# DIO_1.net
KiCad netlist of a schematic drawn in Altium Designer
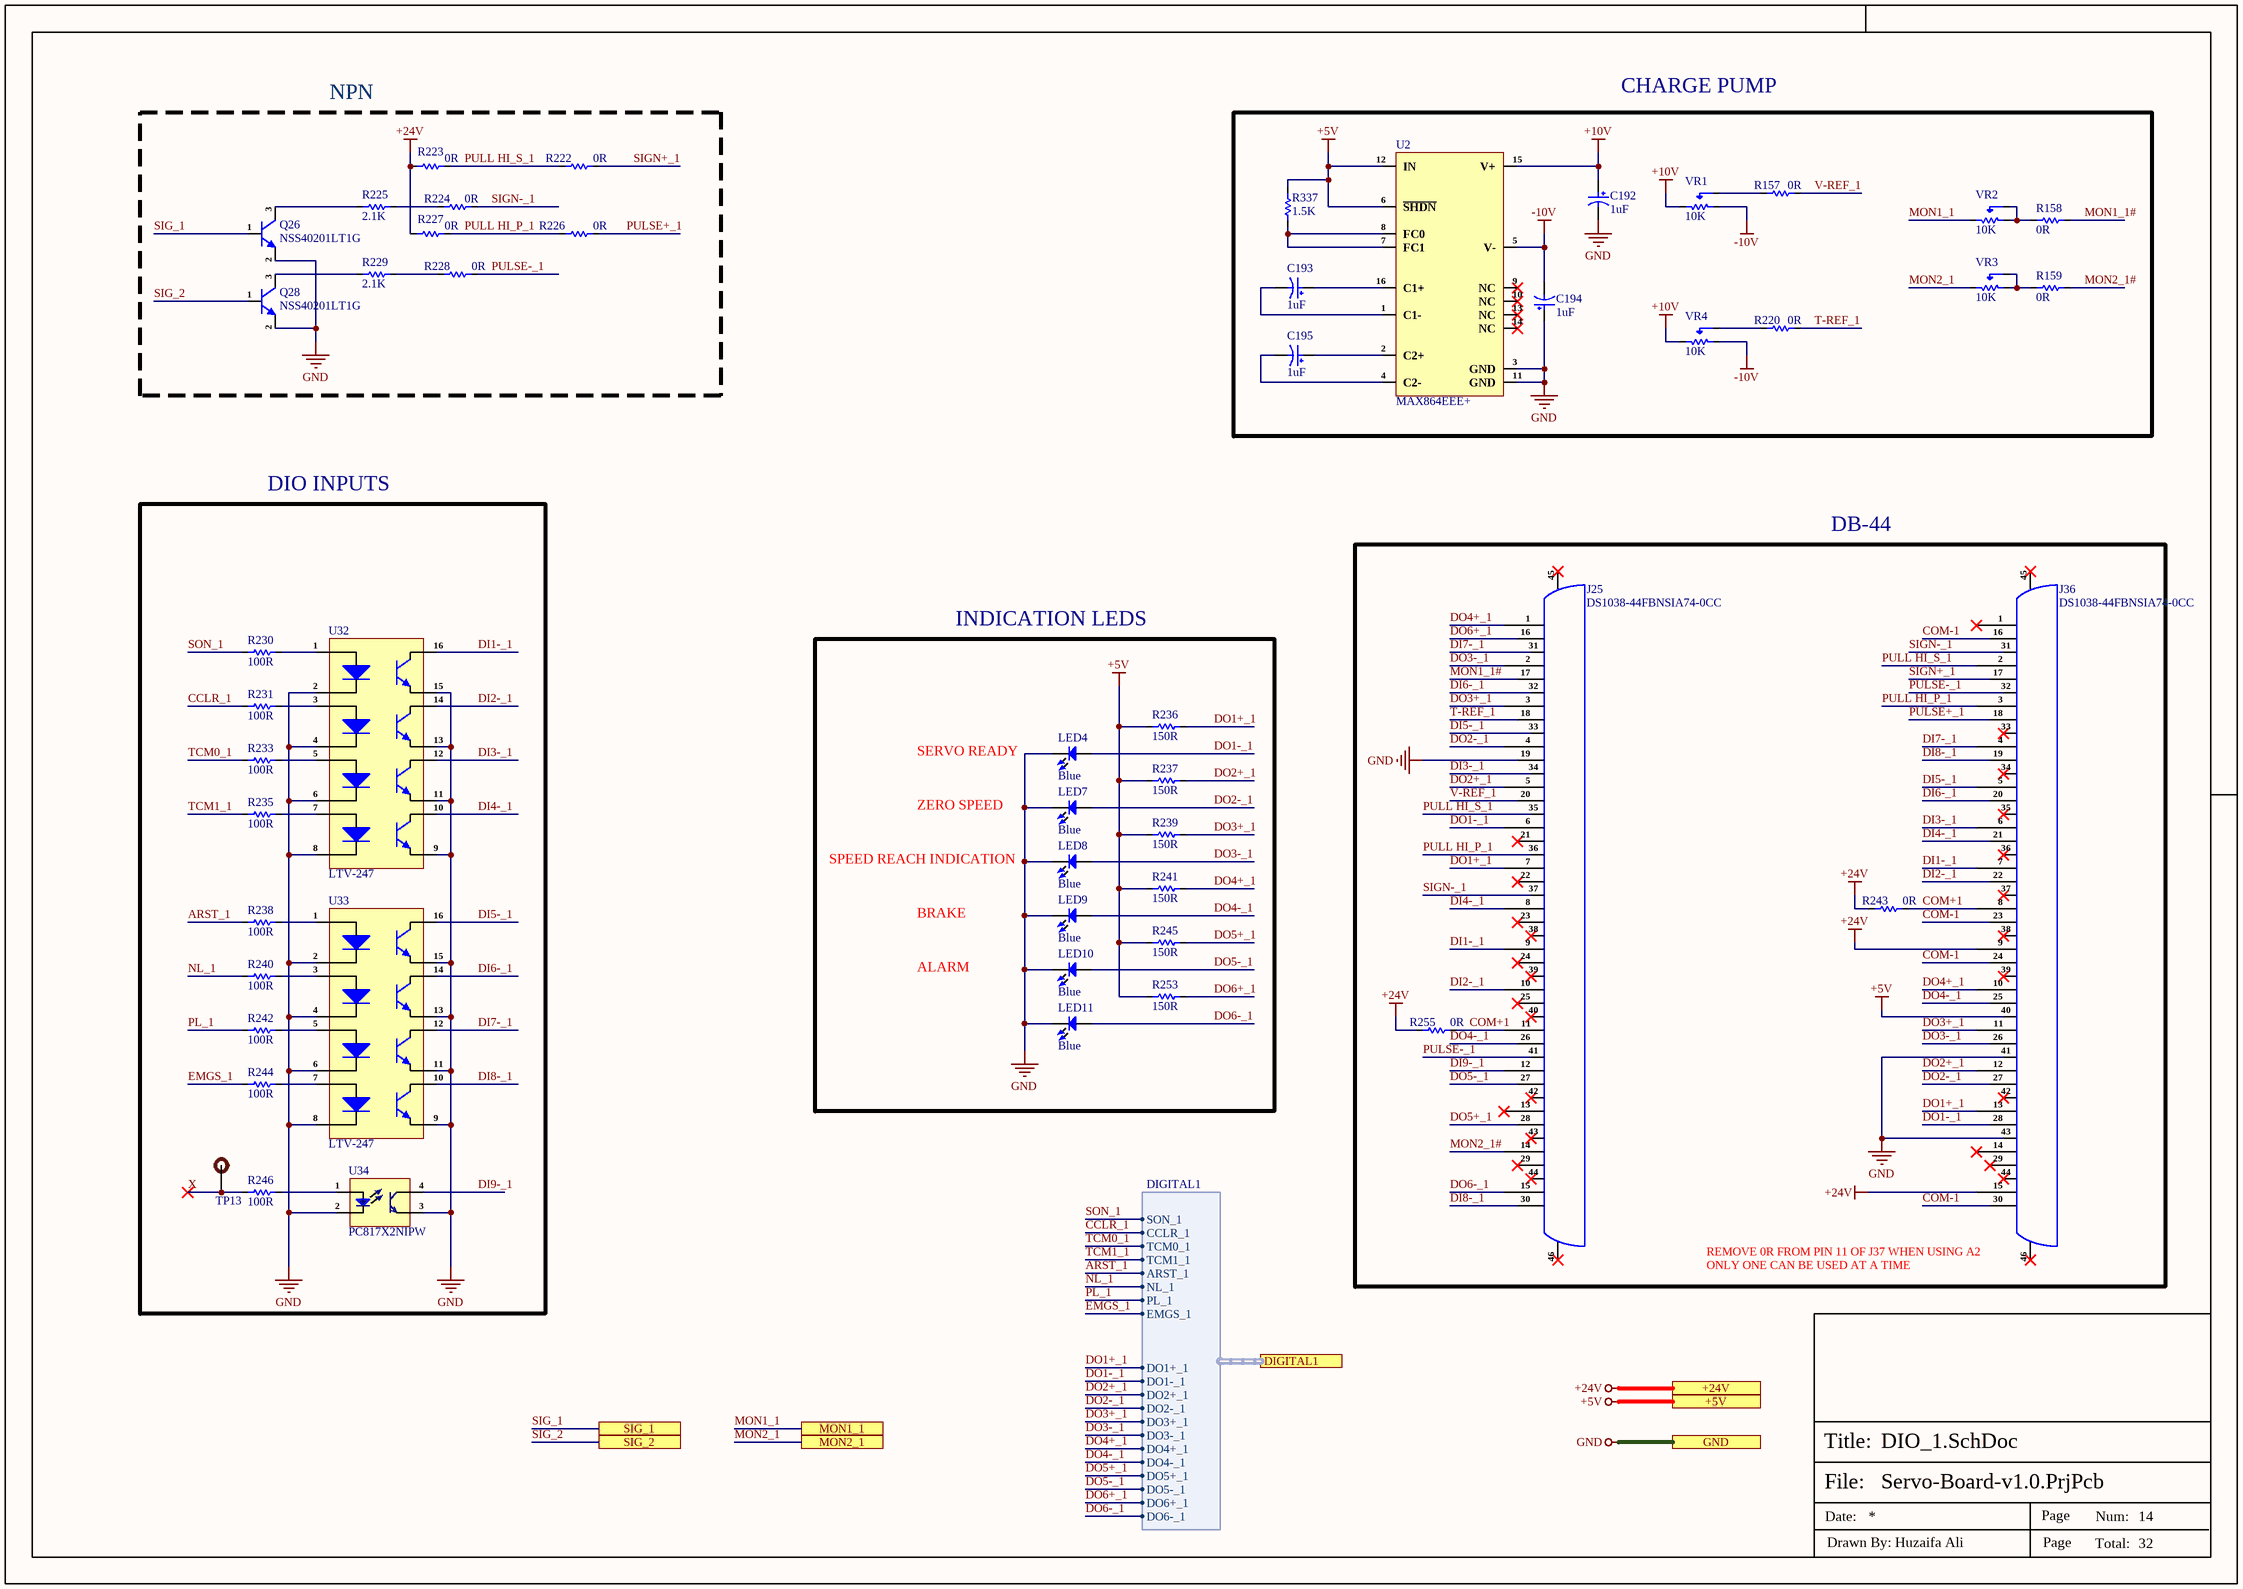
[diagram p0: DIO_1.SchDoc]

(export (version "E")
  (design (tool "Eeschema 10.0.6"))
  (components
    (comp (ref "C192")
      (value "1uF")
      (footprint "RVT1H1R0M0405")
      (description "1uF 50V 8mA@120Hz ±20% SMD,D4xL5.4mm Aluminum Electrolytic Capacitors - SMD ROHS")
      (fields (field (name "LCSC PART NUMBER") "C72491") (field (name "MANUFACTURER") "Roqang"))
      (libsource (lib "") (part "RVT1H1R0M0405_1"))
    )
    (comp (ref "C193")
      (value "1uF")
      (footprint "RVT1H1R0M0405")
      (description "1uF 50V 8mA@120Hz ±20% SMD,D4xL5.4mm Aluminum Electrolytic Capacitors - SMD ROHS")
      (fields (field (name "LCSC PART NUMBER") "C72491") (field (name "MANUFACTURER") "Roqang"))
      (libsource (lib "eSpark Libraries") (part "RVT1H1R0M0405"))
    )
    (comp (ref "C194")
      (value "1uF")
      (footprint "RVT1H1R0M0405")
      (description "1uF 50V 8mA@120Hz ±20% SMD,D4xL5.4mm Aluminum Electrolytic Capacitors - SMD ROHS")
      (fields (field (name "LCSC PART NUMBER") "C72491") (field (name "MANUFACTURER") "Roqang"))
      (libsource (lib "") (part "RVT1H1R0M0405_2"))
    )
    (comp (ref "C195")
      (value "1uF")
      (footprint "RVT1H1R0M0405")
      (description "1uF 50V 8mA@120Hz ±20% SMD,D4xL5.4mm Aluminum Electrolytic Capacitors - SMD ROHS")
      (fields (field (name "LCSC PART NUMBER") "C72491") (field (name "MANUFACTURER") "Roqang"))
      (libsource (lib "eSpark Libraries") (part "RVT1H1R0M0405"))
    )
    (comp (ref "J25")
      (value "DS1038-44FBNSIA74-0CC")
      (footprint "DS1038-44FBNSIA74-0CC")
      (description "44P Female D-Sub Right-Angle 3 1.5A -40℃~+105℃ Push-Pull D-Sub / VGA connector ROHS")
      (fields (field (name "MANUFACTURER") "CONNFLY Elec") (field (name "LCSC PART NUMBER") "C77844"))
      (libsource (lib "eSpark Libraries") (part "DS1038-44FBNSIA74-0CC"))
    )
    (comp (ref "J36")
      (value "DS1038-44FBNSIA74-0CC")
      (footprint "DS1038-44FBNSIA74-0CC")
      (description "44P Female D-Sub Right-Angle 3 1.5A -40℃~+105℃ Push-Pull D-Sub / VGA connector ROHS")
      (fields (field (name "MANUFACTURER") "CONNFLY Elec") (field (name "LCSC PART NUMBER") "C77844"))
      (libsource (lib "eSpark Libraries") (part "DS1038-44FBNSIA74-0CC"))
    )
    (comp (ref "LED4")
      (value "Blue")
      (footprint "LED-0603")
      (description "blue 0603 Light Emitting Diodes (LED) ROHS")
      (fields
        (field (name "MANUFACTURER") "Foshan NationStar Optoelectronics")
        (field (name "MANUFACTURER PART NUMBER") "NCD0603B3")
      )
      (libsource (lib "eSpark Libraries") (part "NCD0603B3"))
    )
    (comp (ref "LED7")
      (value "Blue")
      (footprint "LED-0603")
      (description "blue 0603 Light Emitting Diodes (LED) ROHS")
      (fields
        (field (name "MANUFACTURER") "Foshan NationStar Optoelectronics")
        (field (name "MANUFACTURER PART NUMBER") "NCD0603B3")
      )
      (libsource (lib "eSpark Libraries") (part "NCD0603B3"))
    )
    (comp (ref "LED8")
      (value "Blue")
      (footprint "LED-0603")
      (description "blue 0603 Light Emitting Diodes (LED) ROHS")
      (fields
        (field (name "MANUFACTURER") "Foshan NationStar Optoelectronics")
        (field (name "MANUFACTURER PART NUMBER") "NCD0603B3")
      )
      (libsource (lib "eSpark Libraries") (part "NCD0603B3"))
    )
    (comp (ref "LED9")
      (value "Blue")
      (footprint "LED-0603")
      (description "blue 0603 Light Emitting Diodes (LED) ROHS")
      (fields
        (field (name "MANUFACTURER") "Foshan NationStar Optoelectronics")
        (field (name "MANUFACTURER PART NUMBER") "NCD0603B3")
      )
      (libsource (lib "eSpark Libraries") (part "NCD0603B3"))
    )
    (comp (ref "LED10")
      (value "Blue")
      (footprint "LED-0603")
      (description "blue 0603 Light Emitting Diodes (LED) ROHS")
      (fields
        (field (name "MANUFACTURER") "Foshan NationStar Optoelectronics")
        (field (name "MANUFACTURER PART NUMBER") "NCD0603B3")
      )
      (libsource (lib "eSpark Libraries") (part "NCD0603B3"))
    )
    (comp (ref "LED11")
      (value "Blue")
      (footprint "LED-0603")
      (description "blue 0603 Light Emitting Diodes (LED) ROHS")
      (fields
        (field (name "MANUFACTURER") "Foshan NationStar Optoelectronics")
        (field (name "MANUFACTURER PART NUMBER") "NCD0603B3")
      )
      (libsource (lib "eSpark Libraries") (part "NCD0603B3"))
    )
    (comp (ref "Q26")
      (value "NSS40201LT1G")
      (footprint "SOT-23")
      (description "TRANS NPN 40V 2A SOT23-3")
      (fields (field (name "MANUFACTURER") "ON Semiconductor") (field (name "LCSC PART NUMBER") "C145175"))
      (libsource (lib "eSpark Libraries") (part "NSS40201LT1G"))
    )
    (comp (ref "Q28")
      (value "NSS40201LT1G")
      (footprint "SOT-23")
      (description "TRANS NPN 40V 2A SOT23-3")
      (fields (field (name "MANUFACTURER") "ON Semiconductor") (field (name "LCSC PART NUMBER") "C145175"))
      (libsource (lib "eSpark Libraries") (part "NSS40201LT1G"))
    )
    (comp (ref "R157")
      (value "0R")
      (footprint "Res-0402")
      (description "RES 0 OHM JUMPER 1/16W 0402")
      (fields
        (field (name "MANUFACTURER") "Yageo")
        (field (name "MANUFACTURER PART NUMBER") "RC0402FR-070RL")
      )
      (libsource (lib "eSpark Libraries") (part "RC0402FR-070RL"))
    )
    (comp (ref "R158")
      (value "0R")
      (footprint "Res-0402")
      (description "RES 0 OHM JUMPER 1/16W 0402")
      (fields
        (field (name "MANUFACTURER") "Yageo")
        (field (name "MANUFACTURER PART NUMBER") "RC0402FR-070RL")
      )
      (libsource (lib "eSpark Libraries") (part "RC0402FR-070RL"))
    )
    (comp (ref "R159")
      (value "0R")
      (footprint "Res-0402")
      (description "RES 0 OHM JUMPER 1/16W 0402")
      (fields
        (field (name "MANUFACTURER") "Yageo")
        (field (name "MANUFACTURER PART NUMBER") "RC0402FR-070RL")
      )
      (libsource (lib "eSpark Libraries") (part "RC0402FR-070RL"))
    )
    (comp (ref "R220")
      (value "0R")
      (footprint "Res-0402")
      (description "RES 0 OHM JUMPER 1/16W 0402")
      (fields
        (field (name "MANUFACTURER") "Yageo")
        (field (name "MANUFACTURER PART NUMBER") "RC0402FR-070RL")
      )
      (libsource (lib "eSpark Libraries") (part "RC0402FR-070RL"))
    )
    (comp (ref "R222")
      (value "0R")
      (footprint "Res-0603")
      (description "RES 0 OHM JUMPER 1/10W 0603")
      (fields
        (field (name "MANUFACTURER") "Yageo")
        (field (name "MANUFACTURER PART NUMBER") "RC0603JR-070RL")
      )
      (libsource (lib "eSpark Libraries") (part "RC0603JR-070RL"))
    )
    (comp (ref "R223")
      (value "0R")
      (footprint "Res-0603")
      (description "RES 0 OHM JUMPER 1/10W 0603")
      (fields
        (field (name "MANUFACTURER") "Yageo")
        (field (name "MANUFACTURER PART NUMBER") "RC0603JR-070RL")
      )
      (libsource (lib "eSpark Libraries") (part "RC0603JR-070RL"))
    )
    (comp (ref "R224")
      (value "0R")
      (footprint "Res-0603")
      (description "RES 0 OHM JUMPER 1/10W 0603")
      (fields
        (field (name "MANUFACTURER") "Yageo")
        (field (name "MANUFACTURER PART NUMBER") "RC0603JR-070RL")
      )
      (libsource (lib "eSpark Libraries") (part "RC0603JR-070RL"))
    )
    (comp (ref "R225")
      (value "2.1K")
      (footprint "Res-0603")
      (description "RES SMD 2.1K OHM 0.1% 1/10W 0603")
      (fields
        (field (name "MANUFACTURER") "Yageo")
        (field (name "MANUFACTURER PART NUMBER") "RT0603BRD072K1L")
      )
      (libsource (lib "eSpark Libraries") (part "RT0603BRD072K1L"))
    )
    (comp (ref "R226")
      (value "0R")
      (footprint "Res-0603")
      (description "RES 0 OHM JUMPER 1/10W 0603")
      (fields
        (field (name "MANUFACTURER") "Yageo")
        (field (name "MANUFACTURER PART NUMBER") "RC0603JR-070RL")
      )
      (libsource (lib "eSpark Libraries") (part "RC0603JR-070RL"))
    )
    (comp (ref "R227")
      (value "0R")
      (footprint "Res-0603")
      (description "RES 0 OHM JUMPER 1/10W 0603")
      (fields
        (field (name "MANUFACTURER") "Yageo")
        (field (name "MANUFACTURER PART NUMBER") "RC0603JR-070RL")
      )
      (libsource (lib "eSpark Libraries") (part "RC0603JR-070RL"))
    )
    (comp (ref "R228")
      (value "0R")
      (footprint "Res-0603")
      (description "RES 0 OHM JUMPER 1/10W 0603")
      (fields
        (field (name "MANUFACTURER") "Yageo")
        (field (name "MANUFACTURER PART NUMBER") "RC0603JR-070RL")
      )
      (libsource (lib "eSpark Libraries") (part "RC0603JR-070RL"))
    )
    (comp (ref "R229")
      (value "2.1K")
      (footprint "Res-0603")
      (description "RES SMD 2.1K OHM 0.1% 1/10W 0603")
      (fields
        (field (name "MANUFACTURER") "Yageo")
        (field (name "MANUFACTURER PART NUMBER") "RT0603BRD072K1L")
      )
      (libsource (lib "eSpark Libraries") (part "RT0603BRD072K1L"))
    )
    (comp (ref "R230")
      (value "100R")
      (footprint "Res-0402")
      (description "RES 100 OHM 1% 1/16W 0402")
      (fields
        (field (name "MANUFACTURER") "Yageo")
        (field (name "MANUFACTURER PART NUMBER") "RC0402FR-07100RL")
      )
      (libsource (lib "eSpark Libraries") (part "RC0402FR-07100RL"))
    )
    (comp (ref "R231")
      (value "100R")
      (footprint "Res-0402")
      (description "RES 100 OHM 1% 1/16W 0402")
      (fields
        (field (name "MANUFACTURER") "Yageo")
        (field (name "MANUFACTURER PART NUMBER") "RC0402FR-07100RL")
      )
      (libsource (lib "eSpark Libraries") (part "RC0402FR-07100RL"))
    )
    (comp (ref "R233")
      (value "100R")
      (footprint "Res-0402")
      (description "RES 100 OHM 1% 1/16W 0402")
      (fields
        (field (name "MANUFACTURER") "Yageo")
        (field (name "MANUFACTURER PART NUMBER") "RC0402FR-07100RL")
      )
      (libsource (lib "eSpark Libraries") (part "RC0402FR-07100RL"))
    )
    (comp (ref "R235")
      (value "100R")
      (footprint "Res-0402")
      (description "RES 100 OHM 1% 1/16W 0402")
      (fields
        (field (name "MANUFACTURER") "Yageo")
        (field (name "MANUFACTURER PART NUMBER") "RC0402FR-07100RL")
      )
      (libsource (lib "eSpark Libraries") (part "RC0402FR-07100RL"))
    )
    (comp (ref "R236")
      (value "150R")
      (footprint "Res-0603")
      (description "RES 150 OHM 0.5% 1/10W 0603")
      (fields
        (field (name "MANUFACTURER") "Yageo")
        (field (name "MANUFACTURER PART NUMBER") "RC0603DR-07150RL")
      )
      (libsource (lib "eSpark Libraries") (part "RC0603DR-07150RL"))
    )
    (comp (ref "R237")
      (value "150R")
      (footprint "Res-0603")
      (description "RES 150 OHM 0.5% 1/10W 0603")
      (fields
        (field (name "MANUFACTURER") "Yageo")
        (field (name "MANUFACTURER PART NUMBER") "RC0603DR-07150RL")
      )
      (libsource (lib "eSpark Libraries") (part "RC0603DR-07150RL"))
    )
    (comp (ref "R238")
      (value "100R")
      (footprint "Res-0402")
      (description "RES 100 OHM 1% 1/16W 0402")
      (fields
        (field (name "MANUFACTURER") "Yageo")
        (field (name "MANUFACTURER PART NUMBER") "RC0402FR-07100RL")
      )
      (libsource (lib "eSpark Libraries") (part "RC0402FR-07100RL"))
    )
    (comp (ref "R239")
      (value "150R")
      (footprint "Res-0603")
      (description "RES 150 OHM 0.5% 1/10W 0603")
      (fields
        (field (name "MANUFACTURER") "Yageo")
        (field (name "MANUFACTURER PART NUMBER") "RC0603DR-07150RL")
      )
      (libsource (lib "eSpark Libraries") (part "RC0603DR-07150RL"))
    )
    (comp (ref "R240")
      (value "100R")
      (footprint "Res-0402")
      (description "RES 100 OHM 1% 1/16W 0402")
      (fields
        (field (name "MANUFACTURER") "Yageo")
        (field (name "MANUFACTURER PART NUMBER") "RC0402FR-07100RL")
      )
      (libsource (lib "eSpark Libraries") (part "RC0402FR-07100RL"))
    )
    (comp (ref "R241")
      (value "150R")
      (footprint "Res-0603")
      (description "RES 150 OHM 0.5% 1/10W 0603")
      (fields
        (field (name "MANUFACTURER") "Yageo")
        (field (name "MANUFACTURER PART NUMBER") "RC0603DR-07150RL")
      )
      (libsource (lib "eSpark Libraries") (part "RC0603DR-07150RL"))
    )
    (comp (ref "R242")
      (value "100R")
      (footprint "Res-0402")
      (description "RES 100 OHM 1% 1/16W 0402")
      (fields
        (field (name "MANUFACTURER") "Yageo")
        (field (name "MANUFACTURER PART NUMBER") "RC0402FR-07100RL")
      )
      (libsource (lib "eSpark Libraries") (part "RC0402FR-07100RL"))
    )
    (comp (ref "R243")
      (value "0R")
      (footprint "Res-0402")
      (description "RES 0 OHM JUMPER 1/16W 0402")
      (fields
        (field (name "MANUFACTURER") "Yageo")
        (field (name "MANUFACTURER PART NUMBER") "RC0402FR-070RL")
      )
      (libsource (lib "eSpark Libraries") (part "RC0402FR-070RL"))
    )
    (comp (ref "R244")
      (value "100R")
      (footprint "Res-0402")
      (description "RES 100 OHM 1% 1/16W 0402")
      (fields
        (field (name "MANUFACTURER") "Yageo")
        (field (name "MANUFACTURER PART NUMBER") "RC0402FR-07100RL")
      )
      (libsource (lib "eSpark Libraries") (part "RC0402FR-07100RL"))
    )
    (comp (ref "R245")
      (value "150R")
      (footprint "Res-0603")
      (description "RES 150 OHM 0.5% 1/10W 0603")
      (fields
        (field (name "MANUFACTURER") "Yageo")
        (field (name "MANUFACTURER PART NUMBER") "RC0603DR-07150RL")
      )
      (libsource (lib "eSpark Libraries") (part "RC0603DR-07150RL"))
    )
    (comp (ref "R246")
      (value "100R")
      (footprint "Res-0402")
      (description "RES 100 OHM 1% 1/16W 0402")
      (fields
        (field (name "MANUFACTURER") "Yageo")
        (field (name "MANUFACTURER PART NUMBER") "RC0402FR-07100RL")
      )
      (libsource (lib "eSpark Libraries") (part "RC0402FR-07100RL"))
    )
    (comp (ref "R253")
      (value "150R")
      (footprint "Res-0603")
      (description "RES 150 OHM 0.5% 1/10W 0603")
      (fields
        (field (name "MANUFACTURER") "Yageo")
        (field (name "MANUFACTURER PART NUMBER") "RC0603DR-07150RL")
      )
      (libsource (lib "eSpark Libraries") (part "RC0603DR-07150RL"))
    )
    (comp (ref "R255")
      (value "0R")
      (footprint "Res-0603")
      (description "RES 0 OHM JUMPER 1/10W 0603")
      (fields
        (field (name "MANUFACTURER") "Yageo")
        (field (name "MANUFACTURER PART NUMBER") "RC0603JR-070RL")
      )
      (libsource (lib "eSpark Libraries") (part "RC0603JR-070RL"))
    )
    (comp (ref "R337")
      (value "1.5K")
      (footprint "Res-0402")
      (description "RES 1.5K OHM 1% 1/16W 0402")
      (fields
        (field (name "MANUFACTURER") "Yageo")
        (field (name "MANUFACTURER PART NUMBER") "RC0402FR-071K5L")
      )
      (libsource (lib "eSpark Libraries") (part "RC0402FR-071K5L"))
    )
    (comp (ref "TP13")
      (value "TEST POINT")
      (footprint "Test-point")
      (description "Test Point ON")
      (libsource (lib "eSpark Libraries") (part "TEST POINT"))
    )
    (comp (ref "U2")
      (value "MAX864EEE+")
      (footprint "16-QSOP")
      (description "IC REG CHARGE PUMP INV 16QSOP")
      (fields (field (name "MANUFACTURER") "Maxim"))
      (libsource (lib "eSpark Libraries") (part "MAX864EEE+"))
    )
    (comp (ref "U32")
      (value "LTV-247")
      (footprint "16-SO")
      (description "OPTOISO 3.75KV 4CH TRANS 16SO")
      (fields (field (name "MANUFACTURER") "Vishay Lite-On") (field (name "LCSC PART NUMBER") "C115451"))
      (libsource (lib "eSpark Libraries") (part "LTV-247"))
    )
    (comp (ref "U33")
      (value "LTV-247")
      (footprint "16-SO")
      (description "OPTOISO 3.75KV 4CH TRANS 16SO")
      (fields (field (name "MANUFACTURER") "Vishay Lite-On") (field (name "LCSC PART NUMBER") "C115451"))
      (libsource (lib "eSpark Libraries") (part "LTV-247"))
    )
    (comp (ref "U34")
      (value "PC817X2NIPW")
      (footprint "PC817X2NIPW")
      (description "Optoisolator Output Channel 4-SMD")
      (fields (field (name "MANUFACTURER") "Sharp") (field (name "LCSC PART NUMBER") "C2840443"))
      (libsource (lib "eSpark Libraries") (part "PC817X2NIPW"))
    )
    (comp (ref "VR1")
      (value "10K")
      (footprint "3362P-1-103")
      (description "TRIMMER 10K OHM 0.5W PC PIN TOP")
      (fields (field (name "LCSC PART NUMBER") "C118956") (field (name "MANUFACTURER") "Bourns"))
      (libsource (lib "eSpark Libraries") (part "3362P-1-103"))
    )
    (comp (ref "VR2")
      (value "10K")
      (footprint "3362P-1-103")
      (description "TRIMMER 10K OHM 0.5W PC PIN TOP")
      (fields (field (name "LCSC PART NUMBER") "C118956") (field (name "MANUFACTURER") "Bourns"))
      (libsource (lib "eSpark Libraries") (part "3362P-1-103"))
    )
    (comp (ref "VR3")
      (value "10K")
      (footprint "3362P-1-103")
      (description "TRIMMER 10K OHM 0.5W PC PIN TOP")
      (fields (field (name "LCSC PART NUMBER") "C118956") (field (name "MANUFACTURER") "Bourns"))
      (libsource (lib "eSpark Libraries") (part "3362P-1-103"))
    )
    (comp (ref "VR4")
      (value "10K")
      (footprint "3362P-1-103")
      (description "TRIMMER 10K OHM 0.5W PC PIN TOP")
      (fields (field (name "LCSC PART NUMBER") "C118956") (field (name "MANUFACTURER") "Bourns"))
      (libsource (lib "eSpark Libraries") (part "3362P-1-103"))
    )
  )
  (nets
    (net (code "2") (name "+5V") (class "Default")
      (node (ref "J36") (pin "40") (pinfunction "40_40") (pintype "passive"))
      (node (ref "R236") (pin "1") (pinfunction "1_1") (pintype "passive"))
      (node (ref "R237") (pin "1") (pinfunction "1_1") (pintype "passive"))
      (node (ref "R239") (pin "1") (pinfunction "1_1") (pintype "passive"))
      (node (ref "R241") (pin "1") (pinfunction "1_1") (pintype "passive"))
      (node (ref "R245") (pin "1") (pinfunction "1_1") (pintype "passive"))
      (node (ref "R253") (pin "1") (pinfunction "1_1") (pintype "passive"))
      (node (ref "R337") (pin "2") (pinfunction "2_2") (pintype "passive"))
      (node (ref "U2") (pin "12") (pinfunction "IN_12") (pintype "passive"))
      (node (ref "U2") (pin "6") (pinfunction "~{SHDN}_6") (pintype "passive"))
    )
    (net (code "3") (name "+10V") (class "Default")
      (node (ref "C192") (pin "1") (pintype "passive"))
      (node (ref "U2") (pin "15") (pinfunction "V+_15") (pintype "passive"))
      (node (ref "VR1") (pin "3") (pinfunction "CW_3") (pintype "passive"))
      (node (ref "VR4") (pin "3") (pinfunction "CW_3") (pintype "passive"))
    )
    (net (code "4") (name "+24V") (class "Default")
      (node (ref "J36") (pin "15") (pinfunction "15_15") (pintype "passive"))
      (node (ref "J36") (pin "9") (pinfunction "9_9") (pintype "passive"))
      (node (ref "R223") (pin "1") (pinfunction "1_1") (pintype "passive"))
      (node (ref "R227") (pin "1") (pinfunction "1_1") (pintype "passive"))
      (node (ref "R243") (pin "1") (pinfunction "1_1") (pintype "passive"))
      (node (ref "R255") (pin "1") (pinfunction "1_1") (pintype "passive"))
    )
    (net (code "5") (name "-10V") (class "Default")
      (node (ref "C194") (pin "2") (pintype "passive"))
      (node (ref "U2") (pin "5") (pinfunction "V-_5") (pintype "passive"))
      (node (ref "VR1") (pin "1") (pinfunction "CCW_1") (pintype "passive"))
      (node (ref "VR4") (pin "1") (pinfunction "CCW_1") (pintype "passive"))
    )
    (net (code "6") (name "/ARST_1") (class "Default")
      (node (ref "R238") (pin "1") (pinfunction "1_1") (pintype "passive"))
    )
    (net (code "7") (name "/CCLR_1") (class "Default")
      (node (ref "R231") (pin "1") (pinfunction "1_1") (pintype "passive"))
    )
    (net (code "8") (name "/COM+1") (class "Default")
      (node (ref "J25") (pin "11") (pinfunction "11_11") (pintype "passive"))
      (node (ref "J36") (pin "8") (pinfunction "8_8") (pintype "passive"))
      (node (ref "R243") (pin "2") (pinfunction "2_2") (pintype "passive"))
      (node (ref "R255") (pin "2") (pinfunction "2_2") (pintype "passive"))
    )
    (net (code "9") (name "/COM-1") (class "Default")
      (node (ref "J36") (pin "16") (pinfunction "16_16") (pintype "passive"))
      (node (ref "J36") (pin "23") (pinfunction "23_23") (pintype "passive"))
      (node (ref "J36") (pin "24") (pinfunction "24_24") (pintype "passive"))
      (node (ref "J36") (pin "30") (pinfunction "30_30") (pintype "passive"))
    )
    (net (code "10") (name "/DI1-_1") (class "Default")
      (node (ref "J25") (pin "9") (pinfunction "9_9") (pintype "passive"))
      (node (ref "J36") (pin "7") (pinfunction "7_7") (pintype "passive"))
      (node (ref "U32") (pin "16") (pinfunction "C_16") (pintype "passive"))
    )
    (net (code "11") (name "/DI2-_1") (class "Default")
      (node (ref "J25") (pin "10") (pinfunction "10_10") (pintype "passive"))
      (node (ref "J36") (pin "22") (pinfunction "22_22") (pintype "passive"))
      (node (ref "U32") (pin "14") (pinfunction "C_14") (pintype "passive"))
    )
    (net (code "12") (name "/DI3-_1") (class "Default")
      (node (ref "J25") (pin "34") (pinfunction "34_34") (pintype "passive"))
      (node (ref "J36") (pin "6") (pinfunction "6_6") (pintype "passive"))
      (node (ref "U32") (pin "12") (pinfunction "C_12") (pintype "passive"))
    )
    (net (code "13") (name "/DI4-_1") (class "Default")
      (node (ref "J25") (pin "8") (pinfunction "8_8") (pintype "passive"))
      (node (ref "J36") (pin "21") (pinfunction "21_21") (pintype "passive"))
      (node (ref "U32") (pin "10") (pinfunction "C_10") (pintype "passive"))
    )
    (net (code "14") (name "/DI5-_1") (class "Default")
      (node (ref "J25") (pin "33") (pinfunction "33_33") (pintype "passive"))
      (node (ref "J36") (pin "5") (pinfunction "5_5") (pintype "passive"))
      (node (ref "U33") (pin "16") (pinfunction "C_16") (pintype "passive"))
    )
    (net (code "15") (name "/DI6-_1") (class "Default")
      (node (ref "J25") (pin "32") (pinfunction "32_32") (pintype "passive"))
      (node (ref "J36") (pin "20") (pinfunction "20_20") (pintype "passive"))
      (node (ref "U33") (pin "14") (pinfunction "C_14") (pintype "passive"))
    )
    (net (code "16") (name "/DI7-_1") (class "Default")
      (node (ref "J25") (pin "31") (pinfunction "31_31") (pintype "passive"))
      (node (ref "J36") (pin "4") (pinfunction "4_4") (pintype "passive"))
      (node (ref "U33") (pin "12") (pinfunction "C_12") (pintype "passive"))
    )
    (net (code "17") (name "/DI8-_1") (class "Default")
      (node (ref "J25") (pin "30") (pinfunction "30_30") (pintype "passive"))
      (node (ref "J36") (pin "19") (pinfunction "19_19") (pintype "passive"))
      (node (ref "U33") (pin "10") (pinfunction "C_10") (pintype "passive"))
    )
    (net (code "18") (name "/DI9-_1") (class "Default")
      (node (ref "J25") (pin "12") (pinfunction "12_12") (pintype "passive"))
      (node (ref "U34") (pin "4") (pinfunction "C_4") (pintype "passive"))
    )
    (net (code "19") (name "/DO1+_1") (class "Default")
      (node (ref "J25") (pin "7") (pinfunction "7_7") (pintype "passive"))
      (node (ref "J36") (pin "13") (pinfunction "13_13") (pintype "passive"))
      (node (ref "R236") (pin "2") (pinfunction "2_2") (pintype "passive"))
    )
    (net (code "20") (name "/DO1-_1") (class "Default")
      (node (ref "J25") (pin "6") (pinfunction "6_6") (pintype "passive"))
      (node (ref "J36") (pin "28") (pinfunction "28_28") (pintype "passive"))
      (node (ref "LED4") (pin "1") (pinfunction "1_1") (pintype "passive"))
    )
    (net (code "21") (name "/DO2+_1") (class "Default")
      (node (ref "J25") (pin "5") (pinfunction "5_5") (pintype "passive"))
      (node (ref "J36") (pin "12") (pinfunction "12_12") (pintype "passive"))
      (node (ref "R237") (pin "2") (pinfunction "2_2") (pintype "passive"))
    )
    (net (code "22") (name "/DO2-_1") (class "Default")
      (node (ref "J25") (pin "4") (pinfunction "4_4") (pintype "passive"))
      (node (ref "J36") (pin "27") (pinfunction "27_27") (pintype "passive"))
      (node (ref "LED7") (pin "1") (pinfunction "1_1") (pintype "passive"))
    )
    (net (code "23") (name "/DO3+_1") (class "Default")
      (node (ref "J25") (pin "3") (pinfunction "3_3") (pintype "passive"))
      (node (ref "J36") (pin "11") (pinfunction "11_11") (pintype "passive"))
      (node (ref "R239") (pin "2") (pinfunction "2_2") (pintype "passive"))
    )
    (net (code "24") (name "/DO3-_1") (class "Default")
      (node (ref "J25") (pin "2") (pinfunction "2_2") (pintype "passive"))
      (node (ref "J36") (pin "26") (pinfunction "26_26") (pintype "passive"))
      (node (ref "LED8") (pin "1") (pinfunction "1_1") (pintype "passive"))
    )
    (net (code "25") (name "/DO4+_1") (class "Default")
      (node (ref "J25") (pin "1") (pinfunction "1_1") (pintype "passive"))
      (node (ref "J36") (pin "10") (pinfunction "10_10") (pintype "passive"))
      (node (ref "R241") (pin "2") (pinfunction "2_2") (pintype "passive"))
    )
    (net (code "26") (name "/DO4-_1") (class "Default")
      (node (ref "J25") (pin "26") (pinfunction "26_26") (pintype "passive"))
      (node (ref "J36") (pin "25") (pinfunction "25_25") (pintype "passive"))
      (node (ref "LED9") (pin "1") (pinfunction "1_1") (pintype "passive"))
    )
    (net (code "27") (name "/DO5+_1") (class "Default")
      (node (ref "J25") (pin "28") (pinfunction "28_28") (pintype "passive"))
      (node (ref "R245") (pin "2") (pinfunction "2_2") (pintype "passive"))
    )
    (net (code "28") (name "/DO5-_1") (class "Default")
      (node (ref "J25") (pin "27") (pinfunction "27_27") (pintype "passive"))
      (node (ref "LED10") (pin "1") (pinfunction "1_1") (pintype "passive"))
    )
    (net (code "29") (name "/DO6+_1") (class "Default")
      (node (ref "J25") (pin "16") (pinfunction "16_16") (pintype "passive"))
      (node (ref "R253") (pin "2") (pinfunction "2_2") (pintype "passive"))
    )
    (net (code "30") (name "/DO6-_1") (class "Default")
      (node (ref "J25") (pin "15") (pinfunction "15_15") (pintype "passive"))
      (node (ref "LED11") (pin "1") (pinfunction "1_1") (pintype "passive"))
    )
    (net (code "31") (name "/EMGS_1") (class "Default")
      (node (ref "R244") (pin "1") (pinfunction "1_1") (pintype "passive"))
    )
    (net (code "32") (name "/MON1_1") (class "Default")
      (node (ref "VR2") (pin "3") (pinfunction "CW_3") (pintype "passive"))
    )
    (net (code "33") (name "/MON1_1#") (class "Default")
      (node (ref "J25") (pin "17") (pinfunction "17_17") (pintype "passive"))
      (node (ref "R158") (pin "2") (pinfunction "2_2") (pintype "passive"))
    )
    (net (code "34") (name "/MON2_1") (class "Default")
      (node (ref "VR3") (pin "3") (pinfunction "CW_3") (pintype "passive"))
    )
    (net (code "35") (name "/MON2_1#") (class "Default")
      (node (ref "J25") (pin "14") (pinfunction "14_14") (pintype "passive"))
      (node (ref "R159") (pin "2") (pinfunction "2_2") (pintype "passive"))
    )
    (net (code "36") (name "/NL_1") (class "Default")
      (node (ref "R240") (pin "1") (pinfunction "1_1") (pintype "passive"))
    )
    (net (code "37") (name "/PL_1") (class "Default")
      (node (ref "R242") (pin "1") (pinfunction "1_1") (pintype "passive"))
    )
    (net (code "38") (name "/PULL HI_P_1") (class "Default")
      (node (ref "J25") (pin "36") (pinfunction "36_36") (pintype "passive"))
      (node (ref "J36") (pin "3") (pinfunction "3_3") (pintype "passive"))
      (node (ref "R226") (pin "1") (pinfunction "1_1") (pintype "passive"))
      (node (ref "R227") (pin "2") (pinfunction "2_2") (pintype "passive"))
    )
    (net (code "39") (name "/PULL HI_S_1") (class "Default")
      (node (ref "J25") (pin "35") (pinfunction "35_35") (pintype "passive"))
      (node (ref "J36") (pin "2") (pinfunction "2_2") (pintype "passive"))
      (node (ref "R222") (pin "1") (pinfunction "1_1") (pintype "passive"))
      (node (ref "R223") (pin "2") (pinfunction "2_2") (pintype "passive"))
    )
    (net (code "40") (name "/PULSE+_1") (class "Default")
      (node (ref "J36") (pin "18") (pinfunction "18_18") (pintype "passive"))
      (node (ref "R226") (pin "2") (pinfunction "2_2") (pintype "passive"))
    )
    (net (code "41") (name "/PULSE-_1") (class "Default")
      (node (ref "J25") (pin "41") (pinfunction "41_41") (pintype "passive"))
      (node (ref "J36") (pin "32") (pinfunction "32_32") (pintype "passive"))
      (node (ref "R228") (pin "2") (pinfunction "2_2") (pintype "passive"))
    )
    (net (code "42") (name "/SIGN+_1") (class "Default")
      (node (ref "J36") (pin "17") (pinfunction "17_17") (pintype "passive"))
      (node (ref "R222") (pin "2") (pinfunction "2_2") (pintype "passive"))
    )
    (net (code "43") (name "/SIGN-_1") (class "Default")
      (node (ref "J25") (pin "37") (pinfunction "37_37") (pintype "passive"))
      (node (ref "J36") (pin "31") (pinfunction "31_31") (pintype "passive"))
      (node (ref "R224") (pin "2") (pinfunction "2_2") (pintype "passive"))
    )
    (net (code "44") (name "/SIG_1") (class "Default")
      (node (ref "Q26") (pin "1") (pinfunction "B_1") (pintype "passive"))
    )
    (net (code "45") (name "/SIG_2") (class "Default")
      (node (ref "Q28") (pin "1") (pinfunction "B_1") (pintype "passive"))
    )
    (net (code "46") (name "/SON_1") (class "Default")
      (node (ref "R230") (pin "1") (pinfunction "1_1") (pintype "passive"))
    )
    (net (code "47") (name "/T-REF_1") (class "Default")
      (node (ref "J25") (pin "18") (pinfunction "18_18") (pintype "passive"))
      (node (ref "R220") (pin "2") (pinfunction "2_2") (pintype "passive"))
    )
    (net (code "48") (name "/TCM0_1") (class "Default")
      (node (ref "R233") (pin "1") (pinfunction "1_1") (pintype "passive"))
    )
    (net (code "49") (name "/TCM1_1") (class "Default")
      (node (ref "R235") (pin "1") (pinfunction "1_1") (pintype "passive"))
    )
    (net (code "50") (name "/V-REF_1") (class "Default")
      (node (ref "J25") (pin "20") (pinfunction "20_20") (pintype "passive"))
      (node (ref "R157") (pin "2") (pinfunction "2_2") (pintype "passive"))
    )
    (net (code "51") (name "/X") (class "Default")
      (node (ref "R246") (pin "1") (pinfunction "1_1") (pintype "passive"))
      (node (ref "TP13") (pin "1") (pinfunction "1_1") (pintype "passive"))
    )
    (net (code "53") (name "GND") (class "Default")
      (node (ref "C192") (pin "2") (pintype "passive"))
      (node (ref "C194") (pin "1") (pintype "passive"))
      (node (ref "J25") (pin "19") (pinfunction "19_19") (pintype "passive"))
      (node (ref "J36") (pin "41") (pinfunction "41_41") (pintype "passive"))
      (node (ref "J36") (pin "43") (pinfunction "43_43") (pintype "passive"))
      (node (ref "LED10") (pin "2") (pinfunction "2_2") (pintype "passive"))
      (node (ref "LED11") (pin "2") (pinfunction "2_2") (pintype "passive"))
      (node (ref "LED4") (pin "2") (pinfunction "2_2") (pintype "passive"))
      (node (ref "LED7") (pin "2") (pinfunction "2_2") (pintype "passive"))
      (node (ref "LED8") (pin "2") (pinfunction "2_2") (pintype "passive"))
      (node (ref "LED9") (pin "2") (pinfunction "2_2") (pintype "passive"))
      (node (ref "Q26") (pin "2") (pinfunction "E_2") (pintype "passive"))
      (node (ref "Q28") (pin "2") (pinfunction "E_2") (pintype "passive"))
      (node (ref "U2") (pin "11") (pinfunction "GND_11") (pintype "passive"))
      (node (ref "U2") (pin "3") (pinfunction "GND_3") (pintype "passive"))
      (node (ref "U32") (pin "11") (pinfunction "E_11") (pintype "passive"))
      (node (ref "U32") (pin "13") (pinfunction "E_13") (pintype "passive"))
      (node (ref "U32") (pin "15") (pinfunction "E_15") (pintype "passive"))
      (node (ref "U32") (pin "2") (pinfunction "K_2") (pintype "passive"))
      (node (ref "U32") (pin "4") (pinfunction "K_4") (pintype "passive"))
      (node (ref "U32") (pin "6") (pinfunction "K_6") (pintype "passive"))
      (node (ref "U32") (pin "8") (pinfunction "K_8") (pintype "passive"))
      (node (ref "U32") (pin "9") (pinfunction "E_9") (pintype "passive"))
      (node (ref "U33") (pin "11") (pinfunction "E_11") (pintype "passive"))
      (node (ref "U33") (pin "13") (pinfunction "E_13") (pintype "passive"))
      (node (ref "U33") (pin "15") (pinfunction "E_15") (pintype "passive"))
      (node (ref "U33") (pin "2") (pinfunction "K_2") (pintype "passive"))
      (node (ref "U33") (pin "4") (pinfunction "K_4") (pintype "passive"))
      (node (ref "U33") (pin "6") (pinfunction "K_6") (pintype "passive"))
      (node (ref "U33") (pin "8") (pinfunction "K_8") (pintype "passive"))
      (node (ref "U33") (pin "9") (pinfunction "E_9") (pintype "passive"))
      (node (ref "U34") (pin "2") (pinfunction "Ca_2") (pintype "passive"))
      (node (ref "U34") (pin "3") (pinfunction "E_3") (pintype "passive"))
    )
    (net (code "54") (name "Net-(Q26-C)") (class "Default")
      (node (ref "Q26") (pin "3") (pinfunction "C_3") (pintype "passive"))
      (node (ref "R225") (pin "1") (pinfunction "1_1") (pintype "passive"))
    )
    (net (code "55") (name "Net-(Q28-C)") (class "Default")
      (node (ref "Q28") (pin "3") (pinfunction "C_3") (pintype "passive"))
      (node (ref "R229") (pin "1") (pinfunction "1_1") (pintype "passive"))
    )
    (net (code "56") (name "Net-(R224-Pad1)") (class "Default")
      (node (ref "R224") (pin "1") (pinfunction "1_1") (pintype "passive"))
      (node (ref "R225") (pin "2") (pinfunction "2_2") (pintype "passive"))
    )
    (net (code "57") (name "Net-(R228-Pad1)") (class "Default")
      (node (ref "R228") (pin "1") (pinfunction "1_1") (pintype "passive"))
      (node (ref "R229") (pin "2") (pinfunction "2_2") (pintype "passive"))
    )
    (net (code "58") (name "Net-(R230-Pad2)") (class "Default")
      (node (ref "R230") (pin "2") (pinfunction "2_2") (pintype "passive"))
      (node (ref "U32") (pin "1") (pinfunction "A_1") (pintype "passive"))
    )
    (net (code "59") (name "Net-(R231-Pad2)") (class "Default")
      (node (ref "R231") (pin "2") (pinfunction "2_2") (pintype "passive"))
      (node (ref "U32") (pin "3") (pinfunction "A_3") (pintype "passive"))
    )
    (net (code "60") (name "Net-(R233-Pad2)") (class "Default")
      (node (ref "R233") (pin "2") (pinfunction "2_2") (pintype "passive"))
      (node (ref "U32") (pin "5") (pinfunction "A_5") (pintype "passive"))
    )
    (net (code "61") (name "Net-(R235-Pad2)") (class "Default")
      (node (ref "R235") (pin "2") (pinfunction "2_2") (pintype "passive"))
      (node (ref "U32") (pin "7") (pinfunction "A_7") (pintype "passive"))
    )
    (net (code "62") (name "Net-(R238-Pad2)") (class "Default")
      (node (ref "R238") (pin "2") (pinfunction "2_2") (pintype "passive"))
      (node (ref "U33") (pin "1") (pinfunction "A_1") (pintype "passive"))
    )
    (net (code "63") (name "Net-(R240-Pad2)") (class "Default")
      (node (ref "R240") (pin "2") (pinfunction "2_2") (pintype "passive"))
      (node (ref "U33") (pin "3") (pinfunction "A_3") (pintype "passive"))
    )
    (net (code "64") (name "Net-(R242-Pad2)") (class "Default")
      (node (ref "R242") (pin "2") (pinfunction "2_2") (pintype "passive"))
      (node (ref "U33") (pin "5") (pinfunction "A_5") (pintype "passive"))
    )
    (net (code "65") (name "Net-(R244-Pad2)") (class "Default")
      (node (ref "R244") (pin "2") (pinfunction "2_2") (pintype "passive"))
      (node (ref "U33") (pin "7") (pinfunction "A_7") (pintype "passive"))
    )
    (net (code "66") (name "Net-(U2-C1+)") (class "Default")
      (node (ref "C193") (pin "1") (pintype "passive"))
      (node (ref "U2") (pin "16") (pinfunction "C1+_16") (pintype "passive"))
    )
    (net (code "67") (name "Net-(U2-C1-)") (class "Default")
      (node (ref "C193") (pin "2") (pintype "passive"))
      (node (ref "U2") (pin "1") (pinfunction "C1-_1") (pintype "passive"))
    )
    (net (code "68") (name "Net-(U2-C2+)") (class "Default")
      (node (ref "C195") (pin "1") (pintype "passive"))
      (node (ref "U2") (pin "2") (pinfunction "C2+_2") (pintype "passive"))
    )
    (net (code "69") (name "Net-(U2-C2-)") (class "Default")
      (node (ref "C195") (pin "2") (pintype "passive"))
      (node (ref "U2") (pin "4") (pinfunction "C2-_4") (pintype "passive"))
    )
    (net (code "70") (name "Net-(U2-FC0)") (class "Default")
      (node (ref "R337") (pin "1") (pinfunction "1_1") (pintype "passive"))
      (node (ref "U2") (pin "7") (pinfunction "FC1_7") (pintype "passive"))
      (node (ref "U2") (pin "8") (pinfunction "FC0_8") (pintype "passive"))
    )
    (net (code "71") (name "Net-(U34-An)") (class "Default")
      (node (ref "R246") (pin "2") (pinfunction "2_2") (pintype "passive"))
      (node (ref "U34") (pin "1") (pinfunction "An_1") (pintype "passive"))
    )
    (net (code "72") (name "Net-(VR1-Wiper)") (class "Default")
      (node (ref "R157") (pin "1") (pinfunction "1_1") (pintype "passive"))
      (node (ref "VR1") (pin "2") (pinfunction "Wiper_2") (pintype "passive"))
    )
    (net (code "73") (name "Net-(VR2-CCW)") (class "Default")
      (node (ref "R158") (pin "1") (pinfunction "1_1") (pintype "passive"))
      (node (ref "VR2") (pin "1") (pinfunction "CCW_1") (pintype "passive"))
      (node (ref "VR2") (pin "2") (pinfunction "Wiper_2") (pintype "passive"))
    )
    (net (code "74") (name "Net-(VR3-CCW)") (class "Default")
      (node (ref "R159") (pin "1") (pinfunction "1_1") (pintype "passive"))
      (node (ref "VR3") (pin "1") (pinfunction "CCW_1") (pintype "passive"))
      (node (ref "VR3") (pin "2") (pinfunction "Wiper_2") (pintype "passive"))
    )
    (net (code "75") (name "Net-(VR4-Wiper)") (class "Default")
      (node (ref "R220") (pin "1") (pinfunction "1_1") (pintype "passive"))
      (node (ref "VR4") (pin "2") (pinfunction "Wiper_2") (pintype "passive"))
    )
    (net (code "76") (name "unconnected-(J25-Pad13)") (class "Default")
      (node (ref "J25") (pin "13") (pinfunction "13_13") (pintype "passive+no_connect"))
    )
    (net (code "77") (name "unconnected-(J25-Pad21)") (class "Default")
      (node (ref "J25") (pin "21") (pinfunction "21_21") (pintype "passive+no_connect"))
    )
    (net (code "78") (name "unconnected-(J25-Pad22)") (class "Default")
      (node (ref "J25") (pin "22") (pinfunction "22_22") (pintype "passive+no_connect"))
    )
    (net (code "79") (name "unconnected-(J25-Pad23)") (class "Default")
      (node (ref "J25") (pin "23") (pinfunction "23_23") (pintype "passive+no_connect"))
    )
    (net (code "80") (name "unconnected-(J25-Pad24)") (class "Default")
      (node (ref "J25") (pin "24") (pinfunction "24_24") (pintype "passive+no_connect"))
    )
    (net (code "81") (name "unconnected-(J25-Pad25)") (class "Default")
      (node (ref "J25") (pin "25") (pinfunction "25_25") (pintype "passive+no_connect"))
    )
    (net (code "82") (name "unconnected-(J25-Pad29)") (class "Default")
      (node (ref "J25") (pin "29") (pinfunction "29_29") (pintype "passive+no_connect"))
    )
    (net (code "83") (name "unconnected-(J25-Pad38)") (class "Default")
      (node (ref "J25") (pin "38") (pinfunction "38_38") (pintype "passive+no_connect"))
    )
    (net (code "84") (name "unconnected-(J25-Pad39)") (class "Default")
      (node (ref "J25") (pin "39") (pinfunction "39_39") (pintype "passive+no_connect"))
    )
    (net (code "85") (name "unconnected-(J25-Pad40)") (class "Default")
      (node (ref "J25") (pin "40") (pinfunction "40_40") (pintype "passive+no_connect"))
    )
    (net (code "86") (name "unconnected-(J25-Pad42)") (class "Default")
      (node (ref "J25") (pin "42") (pinfunction "42_42") (pintype "passive+no_connect"))
    )
    (net (code "87") (name "unconnected-(J25-Pad43)") (class "Default")
      (node (ref "J25") (pin "43") (pinfunction "43_43") (pintype "passive+no_connect"))
    )
    (net (code "88") (name "unconnected-(J25-Pad44)") (class "Default")
      (node (ref "J25") (pin "44") (pinfunction "44_44") (pintype "passive+no_connect"))
    )
    (net (code "89") (name "unconnected-(J25-Pad45)") (class "Default")
      (node (ref "J25") (pin "45") (pinfunction "45_45") (pintype "passive+no_connect"))
    )
    (net (code "90") (name "unconnected-(J25-Pad46)") (class "Default")
      (node (ref "J25") (pin "46") (pinfunction "46_46") (pintype "passive+no_connect"))
    )
    (net (code "91") (name "unconnected-(J36-Pad1)") (class "Default")
      (node (ref "J36") (pin "1") (pinfunction "1_1") (pintype "passive+no_connect"))
    )
    (net (code "92") (name "unconnected-(J36-Pad14)") (class "Default")
      (node (ref "J36") (pin "14") (pinfunction "14_14") (pintype "passive+no_connect"))
    )
    (net (code "93") (name "unconnected-(J36-Pad29)") (class "Default")
      (node (ref "J36") (pin "29") (pinfunction "29_29") (pintype "passive+no_connect"))
    )
    (net (code "94") (name "unconnected-(J36-Pad33)") (class "Default")
      (node (ref "J36") (pin "33") (pinfunction "33_33") (pintype "passive+no_connect"))
    )
    (net (code "95") (name "unconnected-(J36-Pad34)") (class "Default")
      (node (ref "J36") (pin "34") (pinfunction "34_34") (pintype "passive+no_connect"))
    )
    (net (code "96") (name "unconnected-(J36-Pad35)") (class "Default")
      (node (ref "J36") (pin "35") (pinfunction "35_35") (pintype "passive+no_connect"))
    )
    (net (code "97") (name "unconnected-(J36-Pad36)") (class "Default")
      (node (ref "J36") (pin "36") (pinfunction "36_36") (pintype "passive+no_connect"))
    )
    (net (code "98") (name "unconnected-(J36-Pad37)") (class "Default")
      (node (ref "J36") (pin "37") (pinfunction "37_37") (pintype "passive+no_connect"))
    )
    (net (code "99") (name "unconnected-(J36-Pad38)") (class "Default")
      (node (ref "J36") (pin "38") (pinfunction "38_38") (pintype "passive+no_connect"))
    )
    (net (code "100") (name "unconnected-(J36-Pad39)") (class "Default")
      (node (ref "J36") (pin "39") (pinfunction "39_39") (pintype "passive+no_connect"))
    )
    (net (code "101") (name "unconnected-(J36-Pad42)") (class "Default")
      (node (ref "J36") (pin "42") (pinfunction "42_42") (pintype "passive+no_connect"))
    )
    (net (code "102") (name "unconnected-(J36-Pad44)") (class "Default")
      (node (ref "J36") (pin "44") (pinfunction "44_44") (pintype "passive+no_connect"))
    )
    (net (code "103") (name "unconnected-(J36-Pad45)") (class "Default")
      (node (ref "J36") (pin "45") (pinfunction "45_45") (pintype "passive+no_connect"))
    )
    (net (code "104") (name "unconnected-(J36-Pad46)") (class "Default")
      (node (ref "J36") (pin "46") (pinfunction "46_46") (pintype "passive+no_connect"))
    )
    (net (code "105") (name "unconnected-(U2-NC-Pad9)") (class "Default")
      (node (ref "U2") (pin "9") (pinfunction "NC_9") (pintype "passive+no_connect"))
    )
    (net (code "106") (name "unconnected-(U2-NC-Pad10)") (class "Default")
      (node (ref "U2") (pin "10") (pinfunction "NC_10") (pintype "passive+no_connect"))
    )
    (net (code "107") (name "unconnected-(U2-NC-Pad13)") (class "Default")
      (node (ref "U2") (pin "13") (pinfunction "NC_13") (pintype "passive+no_connect"))
    )
    (net (code "108") (name "unconnected-(U2-NC-Pad14)") (class "Default")
      (node (ref "U2") (pin "14") (pinfunction "NC_14") (pintype "passive+no_connect"))
    )
  )
)
